# CH340G_CAT-TR.net
KiCad netlist of a schematic drawn in EAGLE
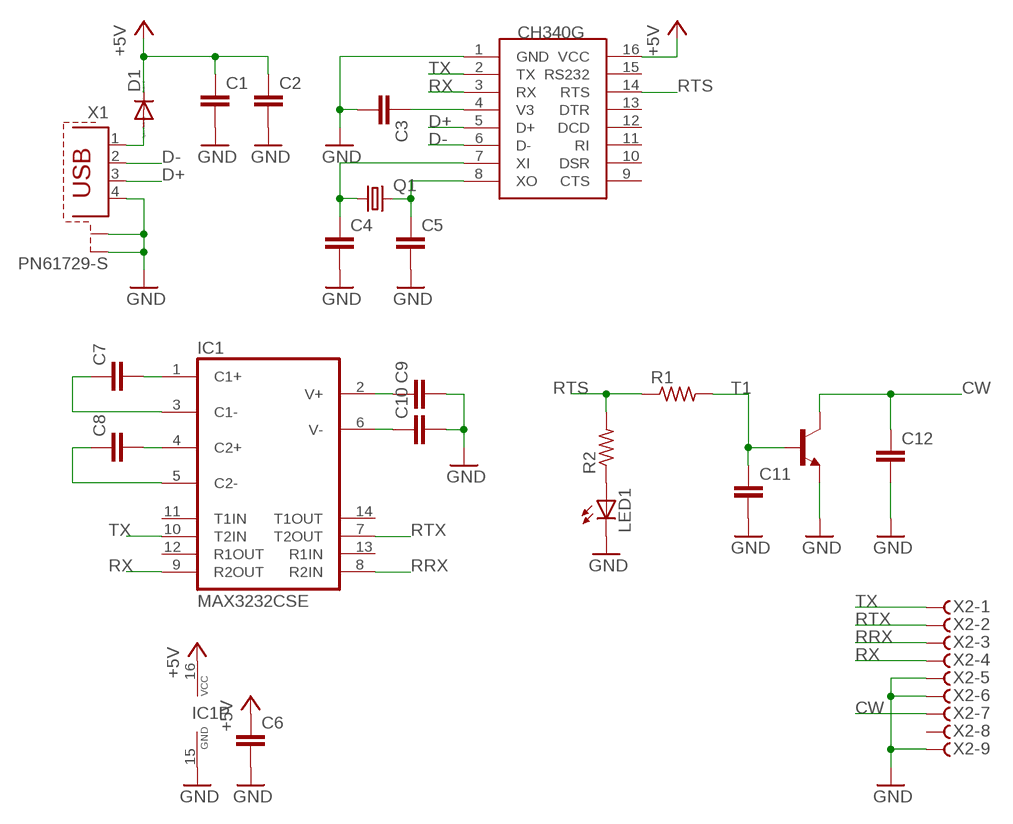
[diagram p0: schematic, sheet 1]

(export (version "E")
  (design (tool "Eeschema 10.0.6"))
  (components
    (comp (ref "C1")
      (value "C-EUC0805K")
      (footprint "eagle-import:C0805K")
      (libsource (lib "eagle-import") (part "C-EUC0805K"))
    )
    (comp (ref "C2")
      (value "C-EUC0805K")
      (footprint "eagle-import:C0805K")
      (libsource (lib "eagle-import") (part "C-EUC0805K"))
    )
    (comp (ref "C3")
      (value "C-EUC0805K")
      (footprint "eagle-import:C0805K")
      (libsource (lib "eagle-import") (part "C-EUC0805K"))
    )
    (comp (ref "C4")
      (value "C-EUC0805K")
      (footprint "eagle-import:C0805K")
      (libsource (lib "eagle-import") (part "C-EUC0805K"))
    )
    (comp (ref "C5")
      (value "C-EUC0805K")
      (footprint "eagle-import:C0805K")
      (libsource (lib "eagle-import") (part "C-EUC0805K"))
    )
    (comp (ref "C6")
      (value "C-EUC0805K")
      (footprint "eagle-import:C0805K")
      (libsource (lib "eagle-import") (part "C-EUC0805K"))
    )
    (comp (ref "C7")
      (value "C-EUC0805K")
      (footprint "eagle-import:C0805K")
      (libsource (lib "eagle-import") (part "C-EUC0805K"))
    )
    (comp (ref "C8")
      (value "C-EUC0805K")
      (footprint "eagle-import:C0805K")
      (libsource (lib "eagle-import") (part "C-EUC0805K"))
    )
    (comp (ref "C9")
      (value "C-EUC0805K")
      (footprint "eagle-import:C0805K")
      (libsource (lib "eagle-import") (part "C-EUC0805K"))
    )
    (comp (ref "C10")
      (value "C-EUC0805K")
      (footprint "eagle-import:C0805K")
      (libsource (lib "eagle-import") (part "C-EUC0805K"))
    )
    (comp (ref "C11")
      (value "C-EUC0805K")
      (footprint "eagle-import:C0805K")
      (libsource (lib "eagle-import") (part "C-EUC0805K"))
    )
    (comp (ref "C12")
      (value "C-EUC0805K")
      (footprint "eagle-import:C0805K")
      (libsource (lib "eagle-import") (part "C-EUC0805K"))
    )
    (comp (ref "D1")
      (value "1N4148DO35-7")
      (footprint "eagle-import:DO35-7")
      (libsource (lib "eagle-import") (part "1N4148DO35-7"))
    )
    (comp (ref "IC1")
      (value "MAX3232CSE")
      (footprint "eagle-import:SO16")
      (libsource (lib "eagle-import") (part "MAX3232SEC"))
    )
    (comp (ref "LED1")
      (value "LED3MM")
      (footprint "eagle-import:LED3MM")
      (libsource (lib "eagle-import") (part "LED3MM"))
    )
    (comp (ref "Q1")
      (value "CRYSTALHC49S")
      (footprint "eagle-import:HC49_S")
      (libsource (lib "eagle-import") (part "CRYSTALHC49S"))
    )
    (comp (ref "R1")
      (value "R-US_M0805")
      (footprint "eagle-import:M0805")
      (libsource (lib "eagle-import") (part "R-US_M0805"))
    )
    (comp (ref "R2")
      (value "R-US_M0805")
      (footprint "eagle-import:M0805")
      (libsource (lib "eagle-import") (part "R-US_M0805"))
    )
    (comp (ref "T1")
      (value "BC548-NPN-TO92-CBE")
      (footprint "eagle-import:TO92-CBE")
      (libsource (lib "eagle-import") (part "-NPN-TO92-CBEBC548"))
    )
    (comp (ref "U$1")
      (value "CH340G")
      (footprint "eagle-import:SOIC16")
      (libsource (lib "eagle-import") (part "CH340G"))
    )
    (comp (ref "X1")
      (value "PN61729-S")
      (footprint "eagle-import:PN61729-S")
      (libsource (lib "eagle-import") (part "PN61729-S"))
    )
    (comp (ref "X2")
      (value "F09HPS")
      (footprint "eagle-import:F09HP")
      (libsource (lib "eagle-import") (part "F09?SHP"))
    )
  )
  (nets
    (net (code "1") (name "+5V") (class "Default")
      (node (ref "C1") (pin "1") (pinfunction "1_1") (pintype "passive"))
      (node (ref "C2") (pin "1") (pinfunction "1_1") (pintype "passive"))
      (node (ref "C6") (pin "1") (pinfunction "1_1") (pintype "passive"))
      (node (ref "D1") (pin "C") (pinfunction "C_C") (pintype "passive"))
      (node (ref "IC1") (pin "16") (pinfunction "VCC_16") (pintype "power_in"))
      (node (ref "U$1") (pin "16") (pinfunction "VCC_16") (pintype "bidirectional"))
    )
    (net (code "2") (name "/CW") (class "Default")
      (node (ref "C12") (pin "1") (pinfunction "1_1") (pintype "passive"))
      (node (ref "T1") (pin "C") (pinfunction "C_C") (pintype "passive"))
      (node (ref "X2") (pin "7") (pinfunction "F_7") (pintype "passive"))
    )
    (net (code "3") (name "/D+") (class "Default")
      (node (ref "U$1") (pin "5") (pinfunction "D+_5") (pintype "bidirectional"))
      (node (ref "X1") (pin "3") (pinfunction "3_3") (pintype "passive"))
    )
    (net (code "4") (name "/D-") (class "Default")
      (node (ref "U$1") (pin "6") (pinfunction "D-_6") (pintype "bidirectional"))
      (node (ref "X1") (pin "2") (pinfunction "2_2") (pintype "passive"))
    )
    (net (code "5") (name "/RRX") (class "Default")
      (node (ref "IC1") (pin "8") (pinfunction "R2IN_8") (pintype "input"))
      (node (ref "X2") (pin "3") (pinfunction "F_3") (pintype "passive"))
    )
    (net (code "6") (name "/RTS") (class "Default")
      (node (ref "R1") (pin "1") (pinfunction "1_1") (pintype "passive"))
      (node (ref "R2") (pin "2") (pinfunction "2_2") (pintype "passive"))
      (node (ref "U$1") (pin "14") (pinfunction "RTS_14") (pintype "bidirectional"))
    )
    (net (code "7") (name "/RTX") (class "Default")
      (node (ref "IC1") (pin "7") (pinfunction "T2OUT_7") (pintype "output"))
      (node (ref "X2") (pin "2") (pinfunction "F_2") (pintype "passive"))
    )
    (net (code "8") (name "/RX") (class "Default")
      (node (ref "IC1") (pin "9") (pinfunction "R2OUT_9") (pintype "output"))
      (node (ref "U$1") (pin "3") (pinfunction "RX_3") (pintype "bidirectional"))
      (node (ref "X2") (pin "4") (pinfunction "F_4") (pintype "passive"))
    )
    (net (code "9") (name "/TX") (class "Default")
      (node (ref "IC1") (pin "10") (pinfunction "T2IN_10") (pintype "input"))
      (node (ref "U$1") (pin "2") (pinfunction "TX_2") (pintype "bidirectional"))
      (node (ref "X2") (pin "1") (pinfunction "F_1") (pintype "passive"))
    )
    (net (code "10") (name "GND") (class "Default")
      (node (ref "C1") (pin "2") (pinfunction "2_2") (pintype "passive"))
      (node (ref "C10") (pin "2") (pinfunction "2_2") (pintype "passive"))
      (node (ref "C11") (pin "2") (pinfunction "2_2") (pintype "passive"))
      (node (ref "C12") (pin "2") (pinfunction "2_2") (pintype "passive"))
      (node (ref "C2") (pin "2") (pinfunction "2_2") (pintype "passive"))
      (node (ref "C3") (pin "2") (pinfunction "2_2") (pintype "passive"))
      (node (ref "C4") (pin "2") (pinfunction "2_2") (pintype "passive"))
      (node (ref "C5") (pin "2") (pinfunction "2_2") (pintype "passive"))
      (node (ref "C6") (pin "2") (pinfunction "2_2") (pintype "passive"))
      (node (ref "C9") (pin "2") (pinfunction "2_2") (pintype "passive"))
      (node (ref "IC1") (pin "15") (pinfunction "GND_15") (pintype "power_in"))
      (node (ref "LED1") (pin "K") (pinfunction "C_K") (pintype "passive"))
      (node (ref "T1") (pin "E") (pinfunction "E_E") (pintype "passive"))
      (node (ref "U$1") (pin "1") (pinfunction "GND_1") (pintype "bidirectional"))
      (node (ref "X1") (pin "4") (pinfunction "4_4") (pintype "passive"))
      (node (ref "X1") (pin "S1") (pinfunction "S1_S1") (pintype "passive"))
      (node (ref "X1") (pin "S2") (pinfunction "S2_S2") (pintype "passive"))
      (node (ref "X2") (pin "5") (pinfunction "F_5") (pintype "passive"))
      (node (ref "X2") (pin "6") (pinfunction "F_6") (pintype "passive"))
      (node (ref "X2") (pin "9") (pinfunction "F_9") (pintype "passive"))
    )
    (net (code "11") (name "Net-(C11-Pad1)") (class "Default")
      (node (ref "C11") (pin "1") (pinfunction "1_1") (pintype "passive"))
      (node (ref "R1") (pin "2") (pinfunction "2_2") (pintype "passive"))
      (node (ref "T1") (pin "B") (pinfunction "B_B") (pintype "passive"))
    )
    (net (code "12") (name "Net-(D1-PadA)") (class "Default")
      (node (ref "D1") (pin "A") (pinfunction "A_A") (pintype "passive"))
      (node (ref "X1") (pin "1") (pinfunction "1_1") (pintype "passive"))
    )
    (net (code "13") (name "Net-(IC1A-C1+)") (class "Default")
      (node (ref "C7") (pin "2") (pinfunction "2_2") (pintype "passive"))
      (node (ref "IC1") (pin "1") (pinfunction "C1+_1") (pintype "bidirectional"))
    )
    (net (code "14") (name "Net-(IC1A-C1-)") (class "Default")
      (node (ref "C7") (pin "1") (pinfunction "1_1") (pintype "passive"))
      (node (ref "IC1") (pin "3") (pinfunction "C1-_3") (pintype "bidirectional"))
    )
    (net (code "15") (name "Net-(IC1A-C2+)") (class "Default")
      (node (ref "C8") (pin "2") (pinfunction "2_2") (pintype "passive"))
      (node (ref "IC1") (pin "4") (pinfunction "C2+_4") (pintype "bidirectional"))
    )
    (net (code "16") (name "Net-(IC1A-C2-)") (class "Default")
      (node (ref "C8") (pin "1") (pinfunction "1_1") (pintype "passive"))
      (node (ref "IC1") (pin "5") (pinfunction "C2-_5") (pintype "bidirectional"))
    )
    (net (code "17") (name "Net-(IC1A-V+)") (class "Default")
      (node (ref "C9") (pin "1") (pinfunction "1_1") (pintype "passive"))
      (node (ref "IC1") (pin "2") (pinfunction "V+_2") (pintype "bidirectional"))
    )
    (net (code "18") (name "Net-(IC1A-V-)") (class "Default")
      (node (ref "C10") (pin "1") (pinfunction "1_1") (pintype "passive"))
      (node (ref "IC1") (pin "6") (pinfunction "V-_6") (pintype "bidirectional"))
    )
    (net (code "19") (name "Net-(LED1-PadA)") (class "Default")
      (node (ref "LED1") (pin "A") (pinfunction "A_A") (pintype "passive"))
      (node (ref "R2") (pin "1") (pinfunction "1_1") (pintype "passive"))
    )
    (net (code "20") (name "Net-(U$1-V3)") (class "Default")
      (node (ref "C3") (pin "1") (pinfunction "1_1") (pintype "passive"))
      (node (ref "U$1") (pin "4") (pinfunction "V3_4") (pintype "bidirectional"))
    )
    (net (code "21") (name "Net-(U$1-XI)") (class "Default")
      (node (ref "C4") (pin "1") (pinfunction "1_1") (pintype "passive"))
      (node (ref "Q1") (pin "1") (pinfunction "1_1") (pintype "passive"))
      (node (ref "U$1") (pin "7") (pinfunction "XI_7") (pintype "bidirectional"))
    )
    (net (code "22") (name "Net-(U$1-XO)") (class "Default")
      (node (ref "C5") (pin "1") (pinfunction "1_1") (pintype "passive"))
      (node (ref "Q1") (pin "2") (pinfunction "2_2") (pintype "passive"))
      (node (ref "U$1") (pin "8") (pinfunction "XO_8") (pintype "bidirectional"))
    )
    (net (code "23") (name "unconnected-(IC1A-R1IN-Pad13)") (class "Default")
      (node (ref "IC1") (pin "13") (pinfunction "R1IN_13") (pintype "input"))
    )
    (net (code "24") (name "unconnected-(IC1A-R1OUT-Pad12)") (class "Default")
      (node (ref "IC1") (pin "12") (pinfunction "R1OUT_12") (pintype "output"))
    )
    (net (code "25") (name "unconnected-(IC1A-T1IN-Pad11)") (class "Default")
      (node (ref "IC1") (pin "11") (pinfunction "T1IN_11") (pintype "input"))
    )
    (net (code "26") (name "unconnected-(IC1A-T1OUT-Pad14)") (class "Default")
      (node (ref "IC1") (pin "14") (pinfunction "T1OUT_14") (pintype "output"))
    )
    (net (code "27") (name "unconnected-(U$1-CTS-Pad9)") (class "Default")
      (node (ref "U$1") (pin "9") (pinfunction "CTS_9") (pintype "bidirectional"))
    )
    (net (code "28") (name "unconnected-(U$1-DCD-Pad12)") (class "Default")
      (node (ref "U$1") (pin "12") (pinfunction "DCD_12") (pintype "bidirectional"))
    )
    (net (code "29") (name "unconnected-(U$1-DSR-Pad10)") (class "Default")
      (node (ref "U$1") (pin "10") (pinfunction "DSR_10") (pintype "bidirectional"))
    )
    (net (code "30") (name "unconnected-(U$1-DTR-Pad13)") (class "Default")
      (node (ref "U$1") (pin "13") (pinfunction "DTR_13") (pintype "bidirectional"))
    )
    (net (code "31") (name "unconnected-(U$1-RI-Pad11)") (class "Default")
      (node (ref "U$1") (pin "11") (pinfunction "RI_11") (pintype "bidirectional"))
    )
    (net (code "32") (name "unconnected-(U$1-RS232-Pad15)") (class "Default")
      (node (ref "U$1") (pin "15") (pinfunction "RS232_15") (pintype "bidirectional"))
    )
    (net (code "33") (name "unconnected-(X2H-F-Pad8)") (class "Default")
      (node (ref "X2") (pin "8") (pinfunction "F_8") (pintype "passive"))
    )
  )
)
